# button.net
KiCad netlist of a schematic drawn in Altium Designer
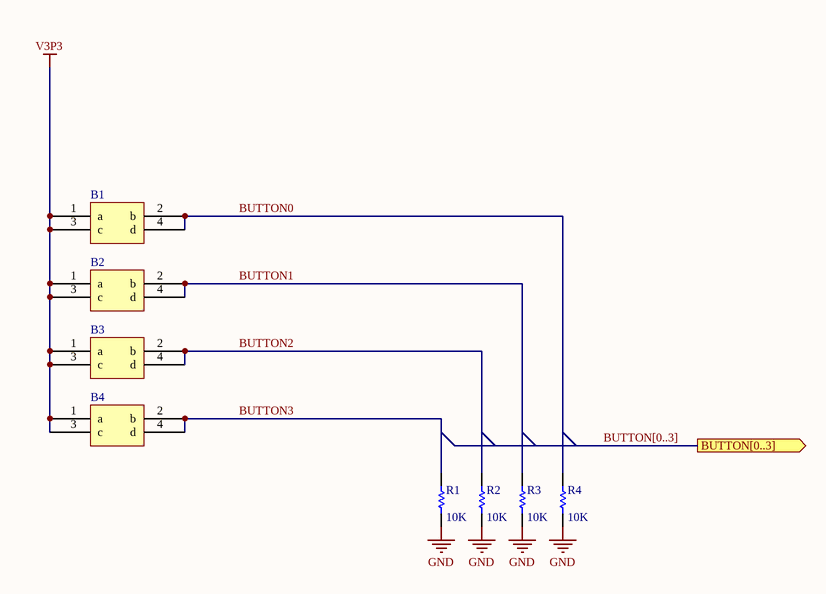
[diagram p0: button.SchDoc]

(export (version "E")
  (design (tool "Eeschema 10.0.6"))
  (components
    (comp (ref "B1")
      (value "ESE20C")
      (footprint "BUTTON_DIS")
      (description "Push switch")
      (libsource (lib "libProject") (part "BUTTON_DIS"))
    )
    (comp (ref "B2")
      (value "ESE20C")
      (footprint "BUTTON_DIS")
      (description "Push switch")
      (libsource (lib "libProject") (part "BUTTON_DIS"))
    )
    (comp (ref "B3")
      (value "ESE20C")
      (footprint "BUTTON_DIS")
      (description "Push switch")
      (libsource (lib "libProject") (part "BUTTON_DIS"))
    )
    (comp (ref "B4")
      (value "ESE20C")
      (footprint "BUTTON_DIS")
      (description "Push switch")
      (libsource (lib "libProject") (part "BUTTON_DIS"))
    )
    (comp (ref "R1")
      (value "10K")
      (footprint "RESISTANCE")
      (description "Resistor")
      (fields (field (name "Comment") "Res1") (field (name "PUBLISHER") "Altium Limited"))
      (libsource (lib "Miscellaneous Devices") (part "Res1"))
    )
    (comp (ref "R2")
      (value "10K")
      (footprint "RESISTANCE")
      (description "Resistor")
      (fields (field (name "Comment") "Res1") (field (name "PUBLISHER") "Altium Limited"))
      (libsource (lib "Miscellaneous Devices") (part "Res1"))
    )
    (comp (ref "R3")
      (value "10K")
      (footprint "RESISTANCE")
      (description "Resistor")
      (fields (field (name "Comment") "Res1") (field (name "PUBLISHER") "Altium Limited"))
      (libsource (lib "Miscellaneous Devices") (part "Res1"))
    )
    (comp (ref "R4")
      (value "10K")
      (footprint "RESISTANCE")
      (description "Resistor")
      (fields (field (name "Comment") "Res1") (field (name "PUBLISHER") "Altium Limited"))
      (libsource (lib "Miscellaneous Devices") (part "Res1"))
    )
  )
  (nets
    (net (code "1") (name "/BUTTON0") (class "Default")
      (node (ref "B1") (pin "2") (pinfunction "b_2") (pintype "passive"))
      (node (ref "B1") (pin "4") (pinfunction "d_4") (pintype "passive"))
      (node (ref "R4") (pin "2") (pinfunction "2_2") (pintype "passive"))
    )
    (net (code "2") (name "/BUTTON1") (class "Default")
      (node (ref "B2") (pin "2") (pinfunction "b_2") (pintype "passive"))
      (node (ref "B2") (pin "4") (pinfunction "d_4") (pintype "passive"))
      (node (ref "R3") (pin "2") (pinfunction "2_2") (pintype "passive"))
    )
    (net (code "3") (name "/BUTTON2") (class "Default")
      (node (ref "B3") (pin "2") (pinfunction "b_2") (pintype "passive"))
      (node (ref "B3") (pin "4") (pinfunction "d_4") (pintype "passive"))
      (node (ref "R2") (pin "2") (pinfunction "2_2") (pintype "passive"))
    )
    (net (code "4") (name "/BUTTON3") (class "Default")
      (node (ref "B4") (pin "2") (pinfunction "b_2") (pintype "passive"))
      (node (ref "B4") (pin "4") (pinfunction "d_4") (pintype "passive"))
      (node (ref "R1") (pin "2") (pinfunction "2_2") (pintype "passive"))
    )
    (net (code "6") (name "GND") (class "Default")
      (node (ref "R1") (pin "1") (pinfunction "1_1") (pintype "passive"))
      (node (ref "R2") (pin "1") (pinfunction "1_1") (pintype "passive"))
      (node (ref "R3") (pin "1") (pinfunction "1_1") (pintype "passive"))
      (node (ref "R4") (pin "1") (pinfunction "1_1") (pintype "passive"))
    )
    (net (code "7") (name "V3P3") (class "Default")
      (node (ref "B1") (pin "1") (pinfunction "a_1") (pintype "passive"))
      (node (ref "B1") (pin "3") (pinfunction "c_3") (pintype "passive"))
      (node (ref "B2") (pin "1") (pinfunction "a_1") (pintype "passive"))
      (node (ref "B2") (pin "3") (pinfunction "c_3") (pintype "passive"))
      (node (ref "B3") (pin "1") (pinfunction "a_1") (pintype "passive"))
      (node (ref "B3") (pin "3") (pinfunction "c_3") (pintype "passive"))
      (node (ref "B4") (pin "1") (pinfunction "a_1") (pintype "passive"))
      (node (ref "B4") (pin "3") (pinfunction "c_3") (pintype "passive"))
    )
  )
)
